# mapleCUx_large_320-002.net
KiCad netlist of a schematic drawn in EAGLE
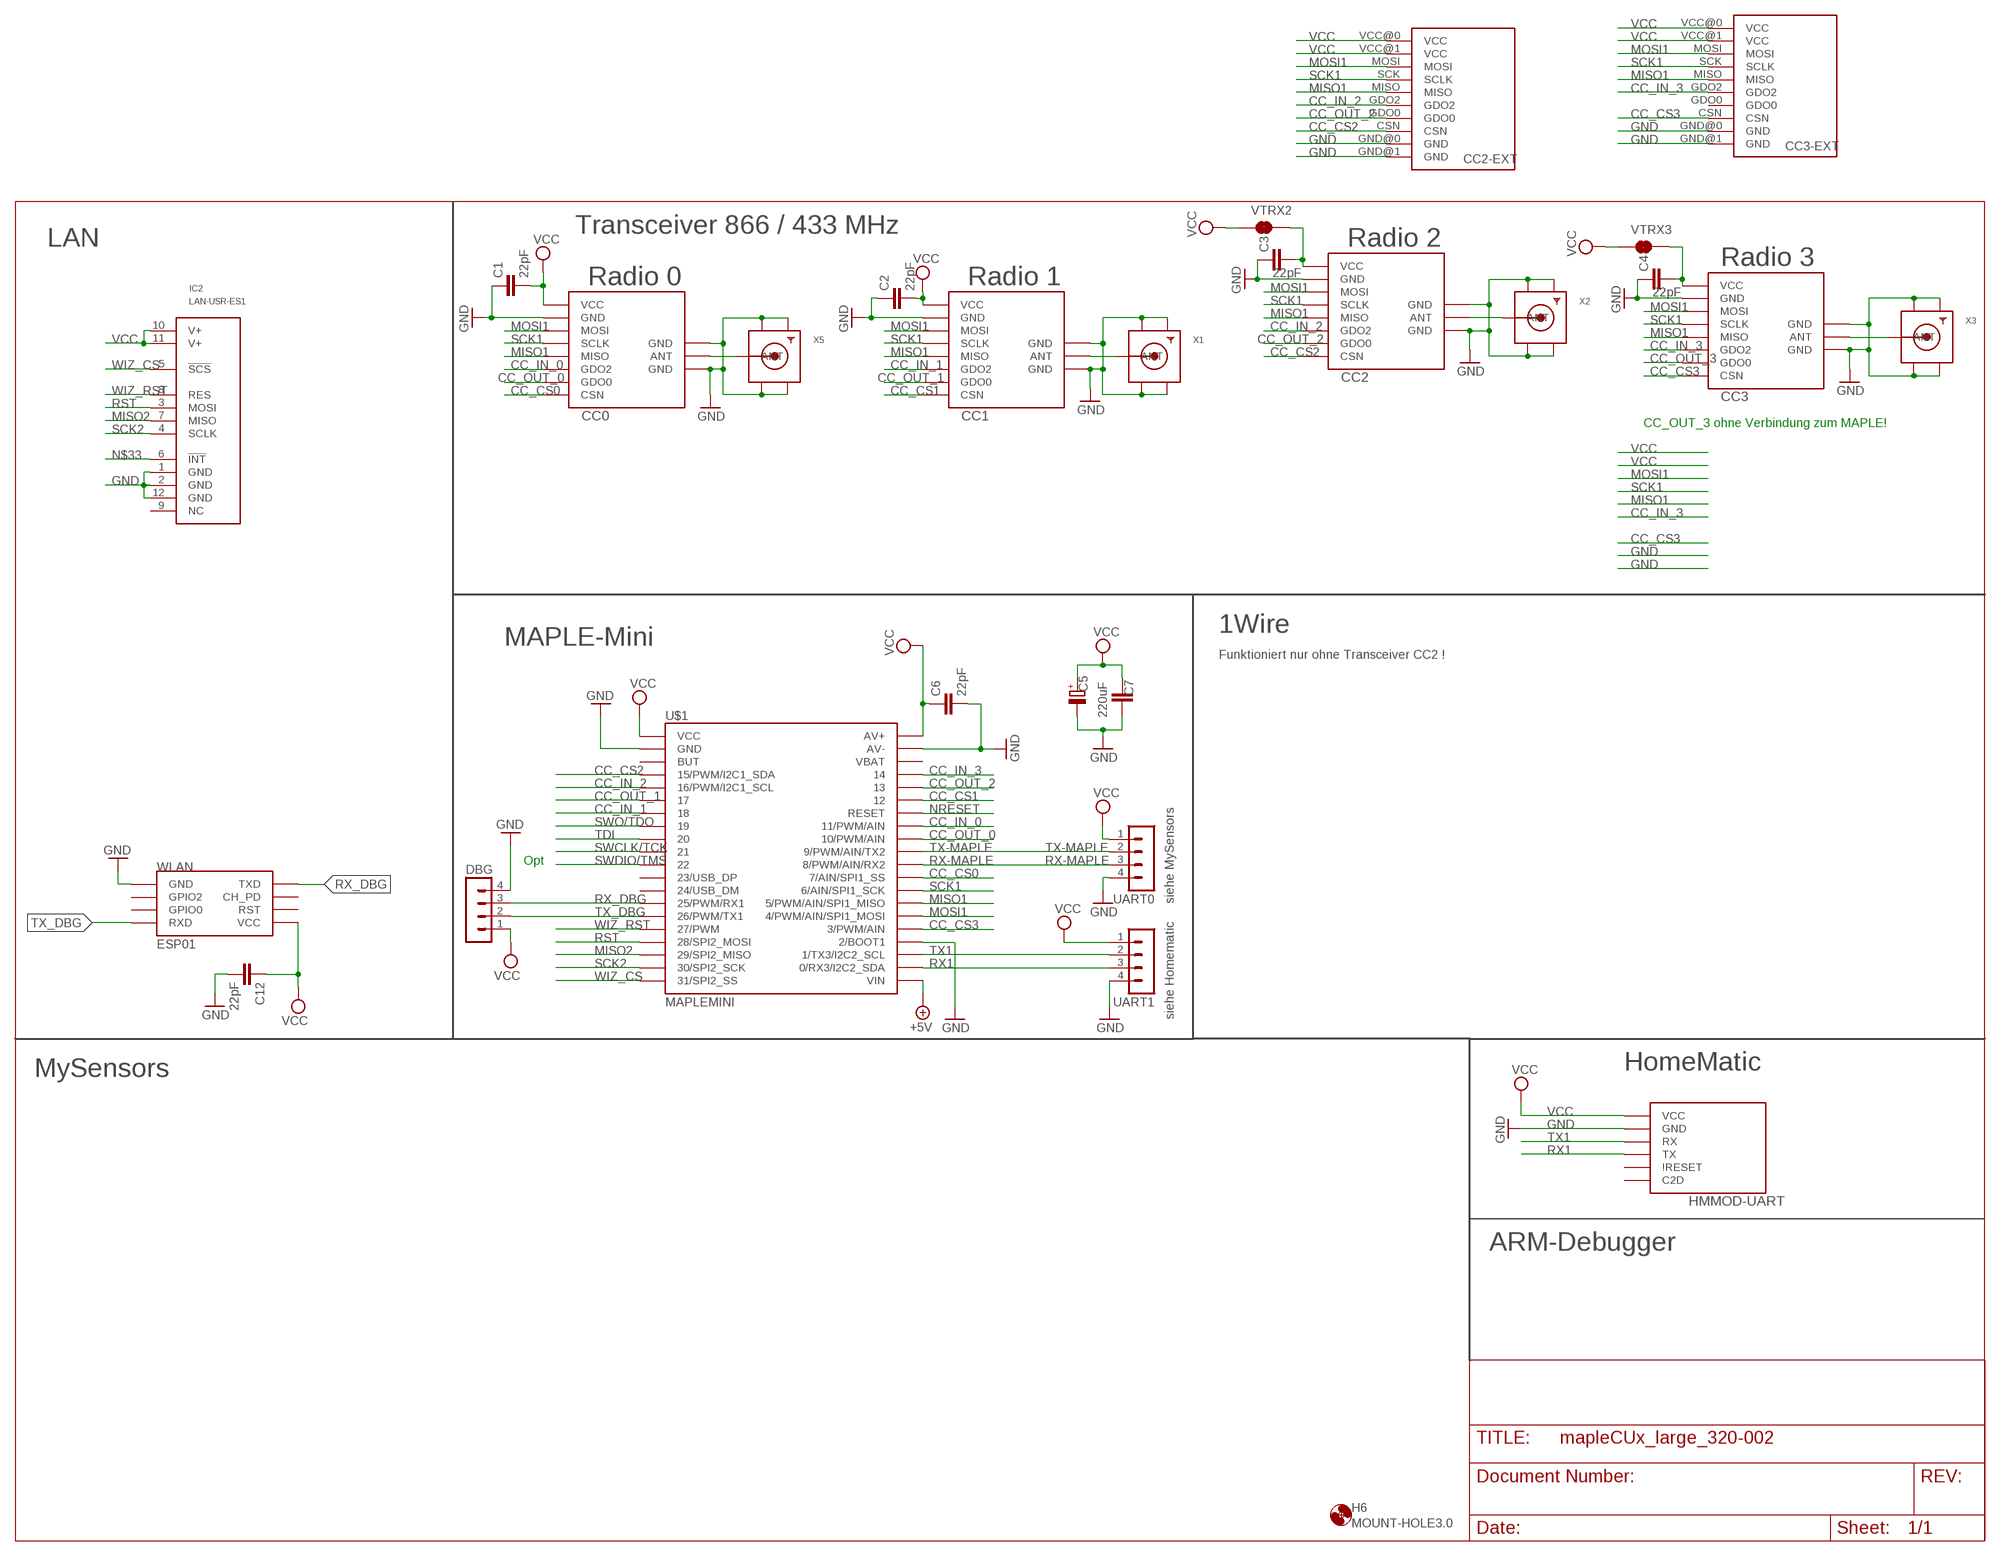
[diagram p0: schematic, sheet 1]

(export (version "E")
  (design (tool "Eeschema 10.0.6"))
  (components
    (comp (ref "C1")
      (value "22pF")
      (footprint "eagle-import:C0805")
      (libsource (lib "eagle-import") (part "C-EUC0805"))
    )
    (comp (ref "C2")
      (value "22pF")
      (footprint "eagle-import:C0805")
      (libsource (lib "eagle-import") (part "C-EUC0805"))
    )
    (comp (ref "C3")
      (value "22pF")
      (footprint "eagle-import:C0805")
      (libsource (lib "eagle-import") (part "C-EUC0805"))
    )
    (comp (ref "C4")
      (value "22pF")
      (footprint "eagle-import:C0805")
      (libsource (lib "eagle-import") (part "C-EUC0805"))
    )
    (comp (ref "C5")
      (value "220uF")
      (footprint "eagle-import:E5-8,5")
      (libsource (lib "eagle-import") (part "CPOL-EUE5-8.5"))
    )
    (comp (ref "C6")
      (value "22pF")
      (footprint "eagle-import:C0805")
      (libsource (lib "eagle-import") (part "C-EUC0805"))
    )
    (comp (ref "C7")
      (value "C-EUC1812")
      (footprint "eagle-import:C1812")
      (libsource (lib "eagle-import") (part "C-EUC1812"))
    )
    (comp (ref "C12")
      (value "22pF")
      (footprint "eagle-import:C0805")
      (libsource (lib "eagle-import") (part "C-EUC0805"))
    )
    (comp (ref "CC0")
      (value "CC1101")
      (footprint "eagle-import:CC1101_MODULE1_SMD")
      (libsource (lib "eagle-import") (part "CC1101_MODULE1SMD"))
    )
    (comp (ref "CC1")
      (value "CC1101_MODULE1SMD")
      (footprint "eagle-import:CC1101_MODULE1_SMD")
      (libsource (lib "eagle-import") (part "CC1101_MODULE1SMD"))
    )
    (comp (ref "CC2")
      (value "CC1101_MODULE1SMD")
      (footprint "eagle-import:CC1101_MODULE1_SMD")
      (libsource (lib "eagle-import") (part "CC1101_MODULE1SMD"))
    )
    (comp (ref "CC2-EXT")
      (value "CC1101_MODULE3_DIL")
      (footprint "eagle-import:CC1101_MODULE3_DIL")
      (libsource (lib "eagle-import") (part "CC1101_MODULE3_DIL"))
    )
    (comp (ref "CC3")
      (value "CC1101_MODULE1SMD")
      (footprint "eagle-import:CC1101_MODULE1_SMD")
      (libsource (lib "eagle-import") (part "CC1101_MODULE1SMD"))
    )
    (comp (ref "CC3-EXT")
      (value "CC1101_MODULE3_DIL")
      (footprint "eagle-import:CC1101_MODULE3_DIL")
      (libsource (lib "eagle-import") (part "CC1101_MODULE3_DIL"))
    )
    (comp (ref "DBG")
      (value "MA04-1")
      (footprint "eagle-import:MA04-1")
      (libsource (lib "eagle-import") (part "MA04-1"))
    )
    (comp (ref "H6")
      (value "MOUNT-HOLE3.0")
      (footprint "eagle-import:3,0")
      (libsource (lib "eagle-import") (part "MOUNT-HOLE3.0"))
    )
    (comp (ref "HMMOD-UART")
      (value "HM-MOD-UARTDIL")
      (footprint "eagle-import:HM-MOD-UART-DIL")
      (libsource (lib "eagle-import") (part "HM-MOD-UARTDIL"))
    )
    (comp (ref "IC2")
      (value "LAN-USR-ES1")
      (footprint "eagle-import:USR-ES1")
      (libsource (lib "eagle-import") (part "LAN-USR-ES1"))
    )
    (comp (ref "U$1")
      (value "MAPLEMINI")
      (footprint "eagle-import:20-DIP")
      (libsource (lib "eagle-import") (part "MAPLEMINI"))
    )
    (comp (ref "UART0")
      (value "MA04-1")
      (footprint "eagle-import:MA04-1")
      (libsource (lib "eagle-import") (part "MA04-1"))
    )
    (comp (ref "UART1")
      (value "MA04-1")
      (footprint "eagle-import:MA04-1")
      (libsource (lib "eagle-import") (part "MA04-1"))
    )
    (comp (ref "VTRX2")
      (value "JUMPER-SMT_2_NC_TRACE_SILK")
      (footprint "eagle-import:SMT-JUMPER_2_NC_TRACE_SILK")
      (libsource (lib "eagle-import") (part "JUMPER-SMT_2_NC_TRACE_SILK"))
    )
    (comp (ref "VTRX3")
      (value "JUMPER-SMT_2_NC_TRACE_SILK")
      (footprint "eagle-import:SMT-JUMPER_2_NC_TRACE_SILK")
      (libsource (lib "eagle-import") (part "JUMPER-SMT_2_NC_TRACE_SILK"))
    )
    (comp (ref "WLAN")
      (value "ESP01")
      (footprint "eagle-import:ESP01")
      (libsource (lib "eagle-import") (part "ESP01"))
    )
    (comp (ref "X1")
      (value "SMACONNECTOR_EDGE")
      (footprint "eagle-import:SMA_EDGELAUNCH")
      (libsource (lib "eagle-import") (part "SMACONNECTOR_EDGE"))
    )
    (comp (ref "X2")
      (value "SMACONNECTOR_EDGE")
      (footprint "eagle-import:SMA_EDGELAUNCH")
      (libsource (lib "eagle-import") (part "SMACONNECTOR_EDGE"))
    )
    (comp (ref "X3")
      (value "SMACONNECTOR_EDGE")
      (footprint "eagle-import:SMA_EDGELAUNCH")
      (libsource (lib "eagle-import") (part "SMACONNECTOR_EDGE"))
    )
    (comp (ref "X5")
      (value "SMACONNECTOR_EDGE")
      (footprint "eagle-import:SMA_EDGELAUNCH")
      (libsource (lib "eagle-import") (part "SMACONNECTOR_EDGE"))
    )
  )
  (nets
    (net (code "1") (name "+5V") (class "Default")
      (node (ref "U$1") (pin "21") (pinfunction "VIN_21") (pintype "bidirectional"))
    )
    (net (code "2") (name "/CC_CS0") (class "Default")
      (node (ref "CC0") (pin "CSN") (pinfunction "CSN_CSN") (pintype "bidirectional"))
      (node (ref "U$1") (pin "29") (pinfunction "7/AIN/SPI1_SS_29") (pintype "bidirectional"))
    )
    (net (code "3") (name "/CC_CS1") (class "Default")
      (node (ref "CC1") (pin "CSN") (pinfunction "CSN_CSN") (pintype "bidirectional"))
      (node (ref "U$1") (pin "35") (pinfunction "12_35") (pintype "bidirectional"))
    )
    (net (code "4") (name "/CC_CS2") (class "Default")
      (node (ref "CC2") (pin "CSN") (pinfunction "CSN_CSN") (pintype "bidirectional"))
      (node (ref "CC2-EXT") (pin "CSN") (pinfunction "CSN_CSN") (pintype "bidirectional"))
      (node (ref "U$1") (pin "4") (pinfunction "15/PWM/I2C1_SDA_4") (pintype "bidirectional"))
    )
    (net (code "5") (name "/CC_CS3") (class "Default")
      (node (ref "CC3") (pin "CSN") (pinfunction "CSN_CSN") (pintype "bidirectional"))
      (node (ref "CC3-EXT") (pin "CSN") (pinfunction "CSN_CSN") (pintype "bidirectional"))
      (node (ref "U$1") (pin "25") (pinfunction "3/PWM/AIN_25") (pintype "bidirectional"))
    )
    (net (code "6") (name "/CC_IN_0") (class "Default")
      (node (ref "CC0") (pin "GDO2") (pinfunction "GDO2_GDO2") (pintype "bidirectional"))
      (node (ref "U$1") (pin "33") (pinfunction "11/PWM/AIN_33") (pintype "bidirectional"))
    )
    (net (code "7") (name "/CC_IN_1") (class "Default")
      (node (ref "CC1") (pin "GDO2") (pinfunction "GDO2_GDO2") (pintype "bidirectional"))
      (node (ref "U$1") (pin "7") (pinfunction "18_7") (pintype "bidirectional"))
    )
    (net (code "8") (name "/CC_IN_2") (class "Default")
      (node (ref "CC2") (pin "GDO2") (pinfunction "GDO2_GDO2") (pintype "bidirectional"))
      (node (ref "CC2-EXT") (pin "GDO2") (pinfunction "GDO2_GDO2") (pintype "bidirectional"))
      (node (ref "U$1") (pin "5") (pinfunction "16/PWM/I2C1_SCL_5") (pintype "bidirectional"))
    )
    (net (code "9") (name "/CC_IN_3") (class "Default")
      (node (ref "CC3") (pin "GDO2") (pinfunction "GDO2_GDO2") (pintype "bidirectional"))
      (node (ref "CC3-EXT") (pin "GDO2") (pinfunction "GDO2_GDO2") (pintype "bidirectional"))
      (node (ref "U$1") (pin "37") (pinfunction "14_37") (pintype "bidirectional"))
    )
    (net (code "10") (name "/CC_OUT_0") (class "Default")
      (node (ref "CC0") (pin "GDO0") (pinfunction "GDO0_GDO0") (pintype "bidirectional"))
      (node (ref "U$1") (pin "32") (pinfunction "10/PWM/AIN_32") (pintype "bidirectional"))
    )
    (net (code "11") (name "/CC_OUT_1") (class "Default")
      (node (ref "CC1") (pin "GDO0") (pinfunction "GDO0_GDO0") (pintype "bidirectional"))
      (node (ref "U$1") (pin "6") (pinfunction "17_6") (pintype "bidirectional"))
    )
    (net (code "12") (name "/CC_OUT_2") (class "Default")
      (node (ref "CC2") (pin "GDO0") (pinfunction "GDO0_GDO0") (pintype "bidirectional"))
      (node (ref "CC2-EXT") (pin "GDO0") (pinfunction "GDO0_GDO0") (pintype "bidirectional"))
      (node (ref "U$1") (pin "36") (pinfunction "13_36") (pintype "bidirectional"))
    )
    (net (code "13") (name "/CC_OUT_3") (class "Default")
      (node (ref "CC3") (pin "GDO0") (pinfunction "GDO0_GDO0") (pintype "bidirectional"))
    )
    (net (code "14") (name "/MISO1") (class "Default")
      (node (ref "CC0") (pin "MISO") (pinfunction "MISO_MISO") (pintype "bidirectional"))
      (node (ref "CC1") (pin "MISO") (pinfunction "MISO_MISO") (pintype "bidirectional"))
      (node (ref "CC2") (pin "MISO") (pinfunction "MISO_MISO") (pintype "bidirectional"))
      (node (ref "CC2-EXT") (pin "MISO") (pinfunction "MISO_MISO") (pintype "bidirectional"))
      (node (ref "CC3") (pin "MISO") (pinfunction "MISO_MISO") (pintype "bidirectional"))
      (node (ref "CC3-EXT") (pin "MISO") (pinfunction "MISO_MISO") (pintype "bidirectional"))
      (node (ref "U$1") (pin "27") (pinfunction "5/PWM/AIN/SPI1_MISO_27") (pintype "bidirectional"))
    )
    (net (code "15") (name "/MISO2") (class "Default")
      (node (ref "IC2") (pin "7") (pinfunction "MISO_7") (pintype "bidirectional"))
      (node (ref "U$1") (pin "18") (pinfunction "29/SPI2_MISO_18") (pintype "bidirectional"))
    )
    (net (code "16") (name "/MOSI1") (class "Default")
      (node (ref "CC0") (pin "MOSI") (pinfunction "MOSI_MOSI") (pintype "bidirectional"))
      (node (ref "CC1") (pin "MOSI") (pinfunction "MOSI_MOSI") (pintype "bidirectional"))
      (node (ref "CC2") (pin "MOSI") (pinfunction "MOSI_MOSI") (pintype "bidirectional"))
      (node (ref "CC2-EXT") (pin "MOSI") (pinfunction "MOSI_MOSI") (pintype "bidirectional"))
      (node (ref "CC3") (pin "MOSI") (pinfunction "MOSI_MOSI") (pintype "bidirectional"))
      (node (ref "CC3-EXT") (pin "MOSI") (pinfunction "MOSI_MOSI") (pintype "bidirectional"))
      (node (ref "U$1") (pin "26") (pinfunction "4/PWM/AIN/SPI1_MOSI_26") (pintype "bidirectional"))
    )
    (net (code "17") (name "/N$33") (class "Default")
      (node (ref "IC2") (pin "6") (pinfunction "~{INT}_6") (pintype "output"))
    )
    (net (code "18") (name "/NRESET") (class "Default")
      (node (ref "U$1") (pin "34") (pinfunction "RESET_34") (pintype "bidirectional"))
    )
    (net (code "19") (name "/RST") (class "Default")
      (node (ref "IC2") (pin "3") (pinfunction "MOSI_3") (pintype "bidirectional"))
      (node (ref "U$1") (pin "17") (pinfunction "28/SPI2_MOSI_17") (pintype "bidirectional"))
    )
    (net (code "20") (name "/RX-MAPLE") (class "Default")
      (node (ref "U$1") (pin "30") (pinfunction "8/PWM/AIN/RX2_30") (pintype "bidirectional"))
      (node (ref "UART0") (pin "3") (pinfunction "3_3") (pintype "passive"))
    )
    (net (code "21") (name "/RX1") (class "Default")
      (node (ref "HMMOD-UART") (pin "5") (pinfunction "TX_5") (pintype "bidirectional"))
      (node (ref "U$1") (pin "22") (pinfunction "0/RX3/I2C2_SDA_22") (pintype "bidirectional"))
      (node (ref "UART1") (pin "3") (pinfunction "3_3") (pintype "passive"))
    )
    (net (code "22") (name "/SCK1") (class "Default")
      (node (ref "CC0") (pin "SCLK") (pinfunction "SCLK_SCLK") (pintype "bidirectional"))
      (node (ref "CC1") (pin "SCLK") (pinfunction "SCLK_SCLK") (pintype "bidirectional"))
      (node (ref "CC2") (pin "SCLK") (pinfunction "SCLK_SCLK") (pintype "bidirectional"))
      (node (ref "CC2-EXT") (pin "SCK") (pinfunction "SCLK_SCK") (pintype "bidirectional"))
      (node (ref "CC3") (pin "SCLK") (pinfunction "SCLK_SCLK") (pintype "bidirectional"))
      (node (ref "CC3-EXT") (pin "SCK") (pinfunction "SCLK_SCK") (pintype "bidirectional"))
      (node (ref "U$1") (pin "28") (pinfunction "6/AIN/SPI1_SCK_28") (pintype "bidirectional"))
    )
    (net (code "23") (name "/SCK2") (class "Default")
      (node (ref "IC2") (pin "4") (pinfunction "SCLK_4") (pintype "input"))
      (node (ref "U$1") (pin "19") (pinfunction "30/SPI2_SCK_19") (pintype "bidirectional"))
    )
    (net (code "24") (name "/SWCLK{slash}TCK") (class "Default")
      (node (ref "U$1") (pin "10") (pinfunction "21_10") (pintype "bidirectional"))
    )
    (net (code "25") (name "/SWDIO{slash}TMS") (class "Default")
      (node (ref "U$1") (pin "11") (pinfunction "22_11") (pintype "bidirectional"))
    )
    (net (code "26") (name "/SWO{slash}TDO") (class "Default")
      (node (ref "U$1") (pin "8") (pinfunction "19_8") (pintype "bidirectional"))
    )
    (net (code "27") (name "/TDI") (class "Default")
      (node (ref "U$1") (pin "9") (pinfunction "20_9") (pintype "bidirectional"))
    )
    (net (code "28") (name "/TX-MAPLE") (class "Default")
      (node (ref "U$1") (pin "31") (pinfunction "9/PWM/AIN/TX2_31") (pintype "bidirectional"))
      (node (ref "UART0") (pin "2") (pinfunction "2_2") (pintype "passive"))
    )
    (net (code "29") (name "/TX1") (class "Default")
      (node (ref "HMMOD-UART") (pin "6") (pinfunction "RX_6") (pintype "bidirectional"))
      (node (ref "U$1") (pin "23") (pinfunction "1/TX3/I2C2_SCL_23") (pintype "bidirectional"))
      (node (ref "UART1") (pin "2") (pinfunction "2_2") (pintype "passive"))
    )
    (net (code "30") (name "/WIZ_CS") (class "Default")
      (node (ref "IC2") (pin "5") (pinfunction "~{SCS}_5") (pintype "input"))
      (node (ref "U$1") (pin "20") (pinfunction "31/SPI2_SS_20") (pintype "bidirectional"))
    )
    (net (code "31") (name "/WIZ_RST") (class "Default")
      (node (ref "IC2") (pin "8") (pinfunction "RES_8") (pintype "input"))
      (node (ref "U$1") (pin "16") (pinfunction "27/PWM_16") (pintype "bidirectional"))
    )
    (net (code "32") (name "GND") (class "Default")
      (node (ref "C1") (pin "1") (pinfunction "1_1") (pintype "passive"))
      (node (ref "C12") (pin "2") (pinfunction "2_2") (pintype "passive"))
      (node (ref "C2") (pin "1") (pinfunction "1_1") (pintype "passive"))
      (node (ref "C3") (pin "1") (pinfunction "1_1") (pintype "passive"))
      (node (ref "C4") (pin "1") (pinfunction "1_1") (pintype "passive"))
      (node (ref "C5") (pin "-") (pinfunction "-_-") (pintype "passive"))
      (node (ref "C6") (pin "2") (pinfunction "2_2") (pintype "passive"))
      (node (ref "C7") (pin "1") (pinfunction "1_1") (pintype "passive"))
      (node (ref "CC0") (pin "GND@0") (pinfunction "GND_GND@0") (pintype "power_in"))
      (node (ref "CC0") (pin "GND@1") (pinfunction "GND_GND@1") (pintype "power_in"))
      (node (ref "CC0") (pin "GND@2") (pinfunction "GND_GND@2") (pintype "power_in"))
      (node (ref "CC1") (pin "GND@0") (pinfunction "GND_GND@0") (pintype "power_in"))
      (node (ref "CC1") (pin "GND@1") (pinfunction "GND_GND@1") (pintype "power_in"))
      (node (ref "CC1") (pin "GND@2") (pinfunction "GND_GND@2") (pintype "power_in"))
      (node (ref "CC2") (pin "GND@0") (pinfunction "GND_GND@0") (pintype "power_in"))
      (node (ref "CC2") (pin "GND@1") (pinfunction "GND_GND@1") (pintype "power_in"))
      (node (ref "CC2") (pin "GND@2") (pinfunction "GND_GND@2") (pintype "power_in"))
      (node (ref "CC2-EXT") (pin "GND@0") (pinfunction "GND_GND@0") (pintype "power_in"))
      (node (ref "CC2-EXT") (pin "GND@1") (pinfunction "GND_GND@1") (pintype "power_in"))
      (node (ref "CC3") (pin "GND@0") (pinfunction "GND_GND@0") (pintype "power_in"))
      (node (ref "CC3") (pin "GND@1") (pinfunction "GND_GND@1") (pintype "power_in"))
      (node (ref "CC3") (pin "GND@2") (pinfunction "GND_GND@2") (pintype "power_in"))
      (node (ref "CC3-EXT") (pin "GND@0") (pinfunction "GND_GND@0") (pintype "power_in"))
      (node (ref "CC3-EXT") (pin "GND@1") (pinfunction "GND_GND@1") (pintype "power_in"))
      (node (ref "DBG") (pin "4") (pinfunction "4_4") (pintype "passive"))
      (node (ref "HMMOD-UART") (pin "2") (pinfunction "GND_2") (pintype "power_in"))
      (node (ref "IC2") (pin "1") (pinfunction "GND_1") (pintype "power_in"))
      (node (ref "IC2") (pin "12") (pinfunction "GND_12") (pintype "power_in"))
      (node (ref "IC2") (pin "2") (pinfunction "GND_2") (pintype "power_in"))
      (node (ref "U$1") (pin "2") (pinfunction "GND_2") (pintype "bidirectional"))
      (node (ref "U$1") (pin "24") (pinfunction "2/BOOT1_24") (pintype "bidirectional"))
      (node (ref "U$1") (pin "39") (pinfunction "AV-_39") (pintype "bidirectional"))
      (node (ref "UART0") (pin "4") (pinfunction "4_4") (pintype "passive"))
      (node (ref "UART1") (pin "4") (pinfunction "4_4") (pintype "passive"))
      (node (ref "WLAN") (pin "GND") (pinfunction "GND_GND") (pintype "bidirectional"))
      (node (ref "X1") (pin "GND@1") (pinfunction "GND4_GND@1") (pintype "power_in"))
      (node (ref "X1") (pin "GND@2") (pinfunction "GND3_GND@2") (pintype "power_in"))
      (node (ref "X1") (pin "GND@3") (pinfunction "GND2_GND@3") (pintype "power_in"))
      (node (ref "X1") (pin "GND@4") (pinfunction "GND1_GND@4") (pintype "power_in"))
      (node (ref "X2") (pin "GND@1") (pinfunction "GND4_GND@1") (pintype "power_in"))
      (node (ref "X2") (pin "GND@2") (pinfunction "GND3_GND@2") (pintype "power_in"))
      (node (ref "X2") (pin "GND@3") (pinfunction "GND2_GND@3") (pintype "power_in"))
      (node (ref "X2") (pin "GND@4") (pinfunction "GND1_GND@4") (pintype "power_in"))
      (node (ref "X3") (pin "GND@1") (pinfunction "GND4_GND@1") (pintype "power_in"))
      (node (ref "X3") (pin "GND@2") (pinfunction "GND3_GND@2") (pintype "power_in"))
      (node (ref "X3") (pin "GND@3") (pinfunction "GND2_GND@3") (pintype "power_in"))
      (node (ref "X3") (pin "GND@4") (pinfunction "GND1_GND@4") (pintype "power_in"))
      (node (ref "X5") (pin "GND@1") (pinfunction "GND4_GND@1") (pintype "power_in"))
      (node (ref "X5") (pin "GND@2") (pinfunction "GND3_GND@2") (pintype "power_in"))
      (node (ref "X5") (pin "GND@3") (pinfunction "GND2_GND@3") (pintype "power_in"))
      (node (ref "X5") (pin "GND@4") (pinfunction "GND1_GND@4") (pintype "power_in"))
    )
    (net (code "33") (name "Net-(C3-Pad2)") (class "Default")
      (node (ref "C3") (pin "2") (pinfunction "2_2") (pintype "passive"))
      (node (ref "CC2") (pin "VCC") (pinfunction "VCC_VCC") (pintype "power_in"))
      (node (ref "VTRX2") (pin "2") (pinfunction "2_2") (pintype "passive"))
    )
    (net (code "34") (name "Net-(C4-Pad2)") (class "Default")
      (node (ref "C4") (pin "2") (pinfunction "2_2") (pintype "passive"))
      (node (ref "CC3") (pin "VCC") (pinfunction "VCC_VCC") (pintype "power_in"))
      (node (ref "VTRX3") (pin "2") (pinfunction "2_2") (pintype "passive"))
    )
    (net (code "35") (name "Net-(X1-ANT)") (class "Default")
      (node (ref "CC1") (pin "ANT") (pinfunction "ANT_ANT") (pintype "output"))
      (node (ref "X1") (pin "P") (pinfunction "ANT_P") (pintype "bidirectional"))
    )
    (net (code "36") (name "Net-(X2-ANT)") (class "Default")
      (node (ref "CC2") (pin "ANT") (pinfunction "ANT_ANT") (pintype "output"))
      (node (ref "X2") (pin "P") (pinfunction "ANT_P") (pintype "bidirectional"))
    )
    (net (code "37") (name "Net-(X3-ANT)") (class "Default")
      (node (ref "CC3") (pin "ANT") (pinfunction "ANT_ANT") (pintype "output"))
      (node (ref "X3") (pin "P") (pinfunction "ANT_P") (pintype "bidirectional"))
    )
    (net (code "38") (name "Net-(X5-ANT)") (class "Default")
      (node (ref "CC0") (pin "ANT") (pinfunction "ANT_ANT") (pintype "output"))
      (node (ref "X5") (pin "P") (pinfunction "ANT_P") (pintype "bidirectional"))
    )
    (net (code "39") (name "RX_DBG") (class "Default")
      (node (ref "DBG") (pin "3") (pinfunction "3_3") (pintype "passive"))
      (node (ref "U$1") (pin "14") (pinfunction "25/PWM/RX1_14") (pintype "bidirectional"))
      (node (ref "WLAN") (pin "TX") (pinfunction "TXD_TX") (pintype "bidirectional"))
    )
    (net (code "40") (name "TX_DBG") (class "Default")
      (node (ref "DBG") (pin "2") (pinfunction "2_2") (pintype "passive"))
      (node (ref "U$1") (pin "15") (pinfunction "26/PWM/TX1_15") (pintype "bidirectional"))
      (node (ref "WLAN") (pin "RX") (pinfunction "RXD_RX") (pintype "bidirectional"))
    )
    (net (code "41") (name "VCC") (class "Default")
      (node (ref "C1") (pin "2") (pinfunction "2_2") (pintype "passive"))
      (node (ref "C12") (pin "1") (pinfunction "1_1") (pintype "passive"))
      (node (ref "C2") (pin "2") (pinfunction "2_2") (pintype "passive"))
      (node (ref "C5") (pin "+") (pinfunction "+_+") (pintype "passive"))
      (node (ref "C6") (pin "1") (pinfunction "1_1") (pintype "passive"))
      (node (ref "C7") (pin "2") (pinfunction "2_2") (pintype "passive"))
      (node (ref "CC0") (pin "VCC") (pinfunction "VCC_VCC") (pintype "power_in"))
      (node (ref "CC1") (pin "VCC") (pinfunction "VCC_VCC") (pintype "power_in"))
      (node (ref "CC2-EXT") (pin "VCC@0") (pinfunction "VCC_VCC@0") (pintype "power_in"))
      (node (ref "CC2-EXT") (pin "VCC@1") (pinfunction "VCC_VCC@1") (pintype "power_in"))
      (node (ref "CC3-EXT") (pin "VCC@0") (pinfunction "VCC_VCC@0") (pintype "power_in"))
      (node (ref "CC3-EXT") (pin "VCC@1") (pinfunction "VCC_VCC@1") (pintype "power_in"))
      (node (ref "DBG") (pin "1") (pinfunction "1_1") (pintype "passive"))
      (node (ref "HMMOD-UART") (pin "1") (pinfunction "VCC_1") (pintype "power_in"))
      (node (ref "IC2") (pin "10") (pinfunction "V+_10") (pintype "power_in"))
      (node (ref "IC2") (pin "11") (pinfunction "V+_11") (pintype "power_in"))
      (node (ref "U$1") (pin "1") (pinfunction "VCC_1") (pintype "bidirectional"))
      (node (ref "U$1") (pin "40") (pinfunction "AV+_40") (pintype "bidirectional"))
      (node (ref "UART0") (pin "1") (pinfunction "1_1") (pintype "passive"))
      (node (ref "UART1") (pin "1") (pinfunction "1_1") (pintype "passive"))
      (node (ref "VTRX2") (pin "1") (pinfunction "1_1") (pintype "passive"))
      (node (ref "VTRX3") (pin "1") (pinfunction "1_1") (pintype "passive"))
      (node (ref "WLAN") (pin "VCC") (pinfunction "VCC_VCC") (pintype "bidirectional"))
    )
    (net (code "42") (name "unconnected-(CC3-EXT-PadGDO0)") (class "Default")
      (node (ref "CC3-EXT") (pin "GDO0") (pinfunction "GDO0_GDO0") (pintype "bidirectional"))
    )
    (net (code "43") (name "unconnected-(HMMOD-UART-C2D-Pad3)") (class "Default")
      (node (ref "HMMOD-UART") (pin "3") (pinfunction "C2D_3") (pintype "bidirectional"))
    )
    (net (code "44") (name "unconnected-(HMMOD-UART-\\~{RESET}-Pad4)") (class "Default")
      (node (ref "HMMOD-UART") (pin "4") (pinfunction "\\~{RESET}_4") (pintype "bidirectional"))
    )
    (net (code "45") (name "unconnected-(IC2-NC-Pad9)") (class "Default")
      (node (ref "IC2") (pin "9") (pinfunction "NC_9") (pintype "no_connect"))
    )
    (net (code "46") (name "unconnected-(U$1-23{slash}USB_DP-Pad12)") (class "Default")
      (node (ref "U$1") (pin "12") (pinfunction "23/USB_DP_12") (pintype "bidirectional"))
    )
    (net (code "47") (name "unconnected-(U$1-24{slash}USB_DM-Pad13)") (class "Default")
      (node (ref "U$1") (pin "13") (pinfunction "24/USB_DM_13") (pintype "bidirectional"))
    )
    (net (code "48") (name "unconnected-(U$1-BUT-Pad3)") (class "Default")
      (node (ref "U$1") (pin "3") (pinfunction "BUT_3") (pintype "bidirectional"))
    )
    (net (code "49") (name "unconnected-(U$1-VBAT-Pad38)") (class "Default")
      (node (ref "U$1") (pin "38") (pinfunction "VBAT_38") (pintype "bidirectional"))
    )
    (net (code "50") (name "unconnected-(WLAN-PadCH_PD)") (class "Default")
      (node (ref "WLAN") (pin "CH_PD") (pinfunction "CH_PD_CH_PD") (pintype "bidirectional"))
    )
    (net (code "51") (name "unconnected-(WLAN-PadGPIO0)") (class "Default")
      (node (ref "WLAN") (pin "GPIO0") (pinfunction "GPIO0_GPIO0") (pintype "bidirectional"))
    )
    (net (code "52") (name "unconnected-(WLAN-PadGPIO2)") (class "Default")
      (node (ref "WLAN") (pin "GPIO2") (pinfunction "GPIO2_GPIO2") (pintype "bidirectional"))
    )
    (net (code "53") (name "unconnected-(WLAN-PadRST)") (class "Default")
      (node (ref "WLAN") (pin "RST") (pinfunction "RST_RST") (pintype "bidirectional"))
    )
  )
)
